# Druckluftelektrik.net
KiCad netlist of a schematic drawn in EAGLE
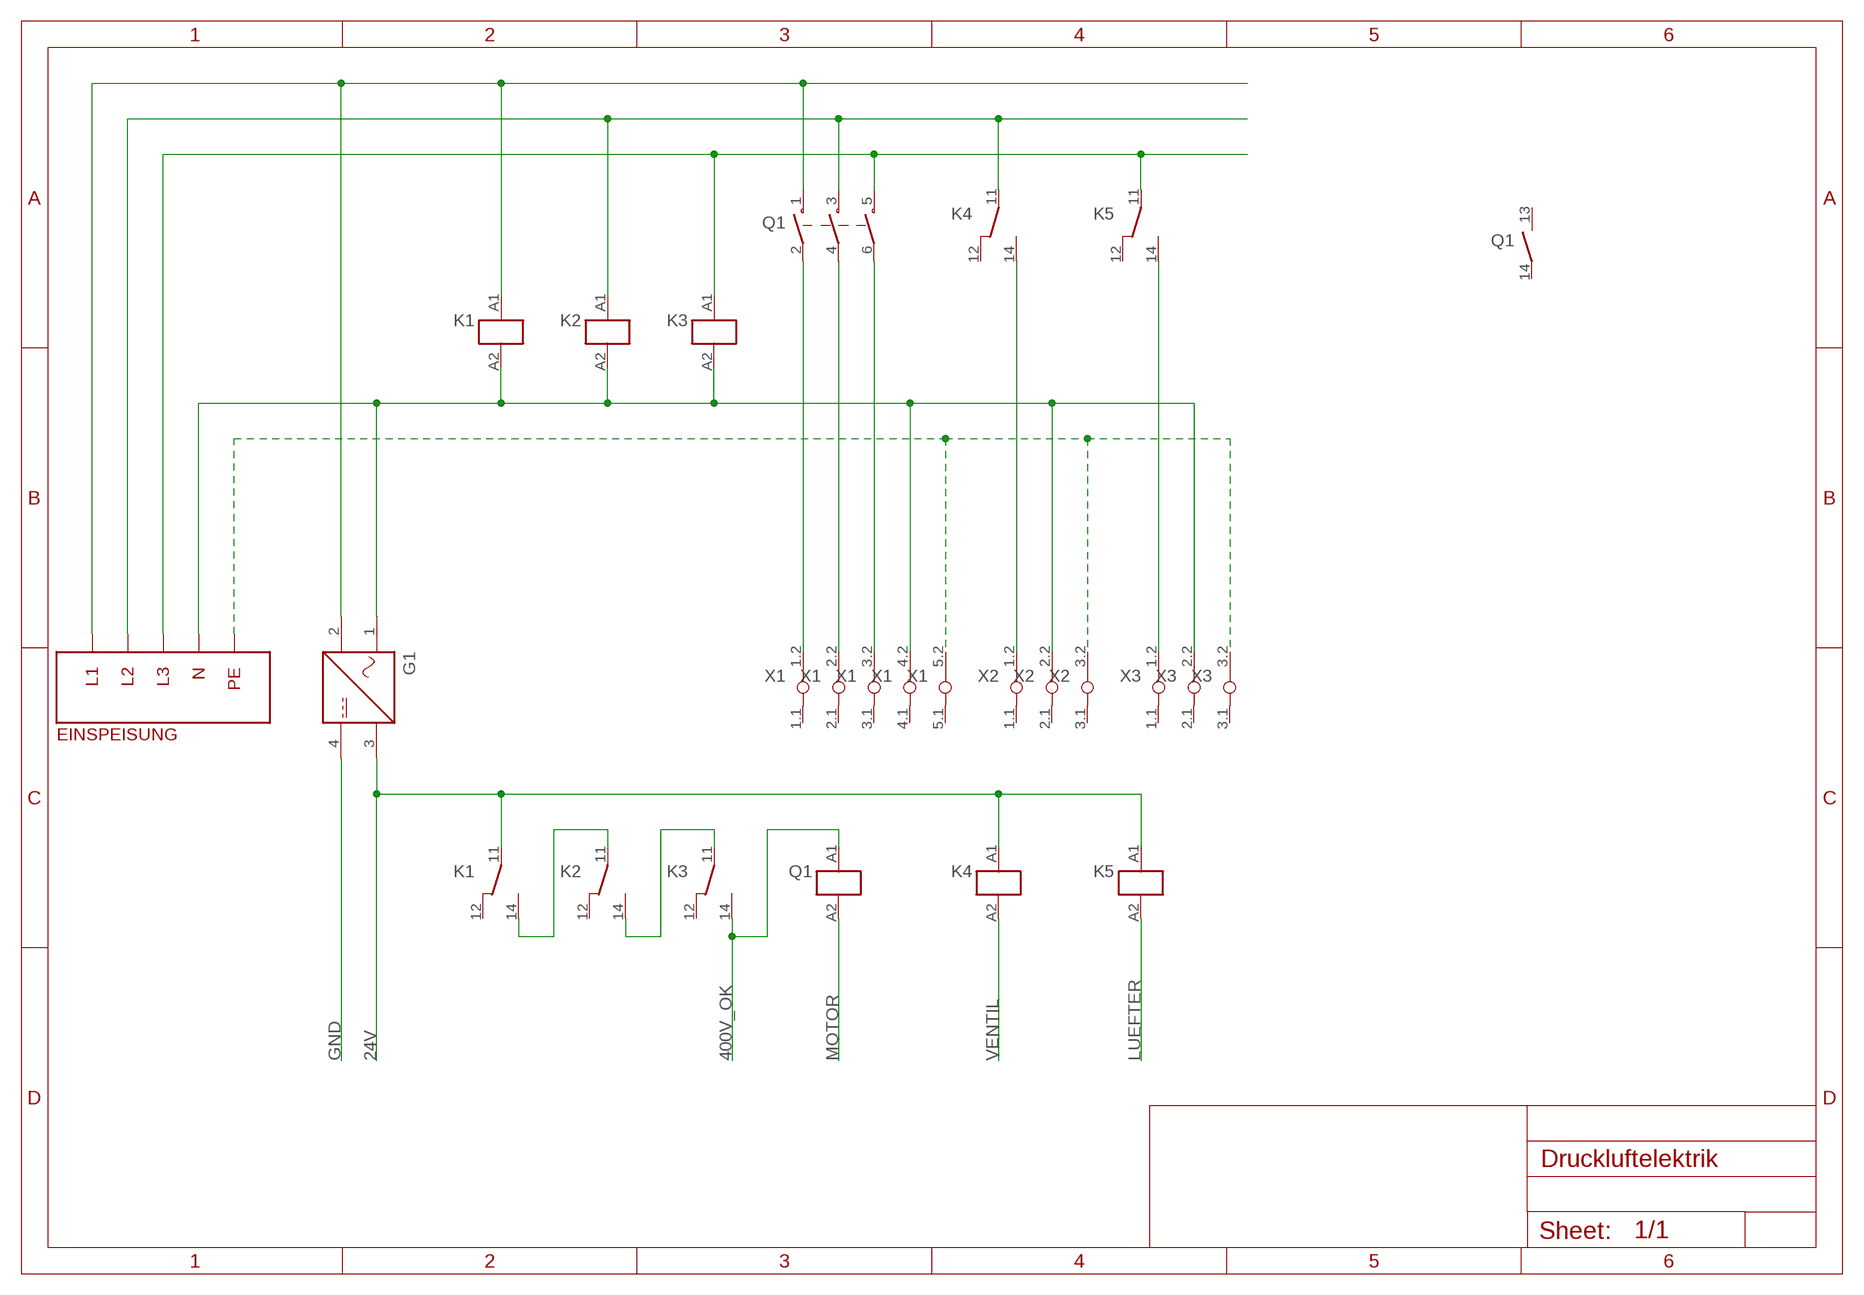
[diagram p0: schematic, sheet 1]

(export (version "E")
  (design (tool "Eeschema 10.0.6"))
  (components
    (comp (ref "G1")
      (value "NETZTEIL_GLEICHSPANNUNG")
      (footprint "eagle-import:NETZTEIL_GLEICHSPANNUNG")
      (libsource (lib "eagle-import") (part "NETZTEIL_GLEICHSPANNUNG"))
    )
    (comp (ref "K1")
      (value "HILFSSCHUETZ_11-12-14")
      (footprint "eagle-import:HILFSSCHUETZ_11-12-14")
      (libsource (lib "eagle-import") (part "HILFSSCHUETZ_11-12-14"))
    )
    (comp (ref "K2")
      (value "HILFSSCHUETZ_11-12-14")
      (footprint "eagle-import:HILFSSCHUETZ_11-12-14")
      (libsource (lib "eagle-import") (part "HILFSSCHUETZ_11-12-14"))
    )
    (comp (ref "K3")
      (value "HILFSSCHUETZ_11-12-14")
      (footprint "eagle-import:HILFSSCHUETZ_11-12-14")
      (libsource (lib "eagle-import") (part "HILFSSCHUETZ_11-12-14"))
    )
    (comp (ref "K4")
      (value "HILFSSCHUETZ_11-12-14")
      (footprint "eagle-import:HILFSSCHUETZ_11-12-14")
      (libsource (lib "eagle-import") (part "HILFSSCHUETZ_11-12-14"))
    )
    (comp (ref "K5")
      (value "HILFSSCHUETZ_11-12-14")
      (footprint "eagle-import:HILFSSCHUETZ_11-12-14")
      (libsource (lib "eagle-import") (part "HILFSSCHUETZ_11-12-14"))
    )
    (comp (ref "Q1")
      (value "HAUPTSCHUETZ_3-POL_HILFSKONTAKT_13-14")
      (footprint "eagle-import:HAUPTSCHUETZ_3-POL+HILFSKONTAKT_13-14")
      (libsource (lib "eagle-import") (part "HAUPTSCHUETZ_3-POL_HILFSKONTAKT_13-14"))
    )
    (comp (ref "X1")
      (value "KLEMME_1-5")
      (footprint "eagle-import:KLEMME_1-5")
      (libsource (lib "eagle-import") (part "KLEMME_1-5"))
    )
    (comp (ref "X2")
      (value "KLEMME_1-3")
      (footprint "eagle-import:KLEMME_1-3")
      (libsource (lib "eagle-import") (part "KLEMME_1-3"))
    )
    (comp (ref "X3")
      (value "KLEMME_1-3")
      (footprint "eagle-import:KLEMME_1-3")
      (libsource (lib "eagle-import") (part "KLEMME_1-3"))
    )
  )
  (nets
    (net (code "1") (name "/24V") (class "Default")
      (node (ref "G1") (pin "3") (pinfunction "3_3") (pintype "passive"))
      (node (ref "K1") (pin "11") (pinfunction "1_11") (pintype "passive"))
      (node (ref "K4") (pin "A1") (pinfunction "A1_A1") (pintype "input"))
      (node (ref "K5") (pin "A1") (pinfunction "A1_A1") (pintype "input"))
    )
    (net (code "2") (name "/400V_OK") (class "Default")
      (node (ref "K3") (pin "14") (pinfunction "4_14") (pintype "passive"))
      (node (ref "Q1") (pin "A1") (pinfunction "A1_A1") (pintype "input"))
    )
    (net (code "3") (name "/GND") (class "Default")
      (node (ref "G1") (pin "4") (pinfunction "4_4") (pintype "passive"))
    )
    (net (code "4") (name "/LUEFTER") (class "Default")
      (node (ref "K5") (pin "A2") (pinfunction "A2_A2") (pintype "input"))
    )
    (net (code "5") (name "/MOTOR") (class "Default")
      (node (ref "Q1") (pin "A2") (pinfunction "A2_A2") (pintype "input"))
    )
    (net (code "6") (name "/VENTIL") (class "Default")
      (node (ref "K4") (pin "A2") (pinfunction "A2_A2") (pintype "input"))
    )
    (net (code "7") (name "Net-(G1-Pad1)") (class "Default")
      (node (ref "G1") (pin "1") (pinfunction "1_1") (pintype "passive"))
      (node (ref "K1") (pin "A2") (pinfunction "A2_A2") (pintype "input"))
      (node (ref "K2") (pin "A2") (pinfunction "A2_A2") (pintype "input"))
      (node (ref "K3") (pin "A2") (pinfunction "A2_A2") (pintype "input"))
      (node (ref "X1") (pin "4.2") (pinfunction "4.2_4.2") (pintype "passive"))
      (node (ref "X2") (pin "2.2") (pinfunction "2.2_2.2") (pintype "passive"))
      (node (ref "X3") (pin "2.2") (pinfunction "2.2_2.2") (pintype "passive"))
    )
    (net (code "8") (name "Net-(G1-Pad2)") (class "Default")
      (node (ref "G1") (pin "2") (pinfunction "2_2") (pintype "passive"))
      (node (ref "K1") (pin "A1") (pinfunction "A1_A1") (pintype "input"))
      (node (ref "Q1") (pin "1") (pinfunction "1_1") (pintype "passive"))
    )
    (net (code "9") (name "Net-(K1B-4)") (class "Default")
      (node (ref "K1") (pin "14") (pinfunction "4_14") (pintype "passive"))
      (node (ref "K2") (pin "11") (pinfunction "1_11") (pintype "passive"))
    )
    (net (code "10") (name "Net-(K2B-4)") (class "Default")
      (node (ref "K2") (pin "14") (pinfunction "4_14") (pintype "passive"))
      (node (ref "K3") (pin "11") (pinfunction "1_11") (pintype "passive"))
    )
    (net (code "11") (name "Net-(K4B-1)") (class "Default")
      (node (ref "K2") (pin "A1") (pinfunction "A1_A1") (pintype "input"))
      (node (ref "K4") (pin "11") (pinfunction "1_11") (pintype "passive"))
      (node (ref "Q1") (pin "3") (pinfunction "3_3") (pintype "passive"))
    )
    (net (code "12") (name "Net-(K4B-4)") (class "Default")
      (node (ref "K4") (pin "14") (pinfunction "4_14") (pintype "passive"))
      (node (ref "X2") (pin "1.2") (pinfunction "1.2_1.2") (pintype "passive"))
    )
    (net (code "13") (name "Net-(K5B-1)") (class "Default")
      (node (ref "K3") (pin "A1") (pinfunction "A1_A1") (pintype "input"))
      (node (ref "K5") (pin "11") (pinfunction "1_11") (pintype "passive"))
      (node (ref "Q1") (pin "5") (pinfunction "5_5") (pintype "passive"))
    )
    (net (code "14") (name "Net-(K5B-4)") (class "Default")
      (node (ref "K5") (pin "14") (pinfunction "4_14") (pintype "passive"))
      (node (ref "X3") (pin "1.2") (pinfunction "1.2_1.2") (pintype "passive"))
    )
    (net (code "15") (name "Net-(Q1-Pad2)") (class "Default")
      (node (ref "Q1") (pin "2") (pinfunction "2_2") (pintype "passive"))
      (node (ref "X1") (pin "1.2") (pinfunction "1.2_1.2") (pintype "passive"))
    )
    (net (code "16") (name "Net-(Q1-Pad4)") (class "Default")
      (node (ref "Q1") (pin "4") (pinfunction "4_4") (pintype "passive"))
      (node (ref "X1") (pin "2.2") (pinfunction "2.2_2.2") (pintype "passive"))
    )
    (net (code "17") (name "Net-(Q1-Pad6)") (class "Default")
      (node (ref "Q1") (pin "6") (pinfunction "6_6") (pintype "passive"))
      (node (ref "X1") (pin "3.2") (pinfunction "3.2_3.2") (pintype "passive"))
    )
    (net (code "18") (name "Net-(X1-Pad5.2)") (class "Default")
      (node (ref "X1") (pin "5.2") (pinfunction "5.2_5.2") (pintype "passive"))
      (node (ref "X2") (pin "3.2") (pinfunction "3.2_3.2") (pintype "passive"))
      (node (ref "X3") (pin "3.2") (pinfunction "3.2_3.2") (pintype "passive"))
    )
    (net (code "19") (name "unconnected-(K1B-2-Pad12)") (class "Default")
      (node (ref "K1") (pin "12") (pinfunction "2_12") (pintype "passive"))
    )
    (net (code "20") (name "unconnected-(K2B-2-Pad12)") (class "Default")
      (node (ref "K2") (pin "12") (pinfunction "2_12") (pintype "passive"))
    )
    (net (code "21") (name "unconnected-(K3B-2-Pad12)") (class "Default")
      (node (ref "K3") (pin "12") (pinfunction "2_12") (pintype "passive"))
    )
    (net (code "22") (name "unconnected-(K4B-2-Pad12)") (class "Default")
      (node (ref "K4") (pin "12") (pinfunction "2_12") (pintype "passive"))
    )
    (net (code "23") (name "unconnected-(K5B-2-Pad12)") (class "Default")
      (node (ref "K5") (pin "12") (pinfunction "2_12") (pintype "passive"))
    )
    (net (code "24") (name "unconnected-(Q1B-3-Pad13)") (class "Default")
      (node (ref "Q1") (pin "13") (pinfunction "3_13") (pintype "passive"))
    )
    (net (code "25") (name "unconnected-(Q1B-4-Pad14)") (class "Default")
      (node (ref "Q1") (pin "14") (pinfunction "4_14") (pintype "passive"))
    )
    (net (code "26") (name "unconnected-(X1-Pad1.1)") (class "Default")
      (node (ref "X1") (pin "1.1") (pinfunction "1.1_1.1") (pintype "passive"))
    )
    (net (code "27") (name "unconnected-(X1-Pad2.1)") (class "Default")
      (node (ref "X1") (pin "2.1") (pinfunction "2.1_2.1") (pintype "passive"))
    )
    (net (code "28") (name "unconnected-(X1-Pad3.1)") (class "Default")
      (node (ref "X1") (pin "3.1") (pinfunction "3.1_3.1") (pintype "passive"))
    )
    (net (code "29") (name "unconnected-(X1-Pad4.1)") (class "Default")
      (node (ref "X1") (pin "4.1") (pinfunction "4.1_4.1") (pintype "passive"))
    )
    (net (code "30") (name "unconnected-(X1-Pad5.1)") (class "Default")
      (node (ref "X1") (pin "5.1") (pinfunction "5.1_5.1") (pintype "passive"))
    )
    (net (code "31") (name "unconnected-(X2-Pad1.1)") (class "Default")
      (node (ref "X2") (pin "1.1") (pinfunction "1.1_1.1") (pintype "passive"))
    )
    (net (code "32") (name "unconnected-(X2-Pad2.1)") (class "Default")
      (node (ref "X2") (pin "2.1") (pinfunction "2.1_2.1") (pintype "passive"))
    )
    (net (code "33") (name "unconnected-(X2-Pad3.1)") (class "Default")
      (node (ref "X2") (pin "3.1") (pinfunction "3.1_3.1") (pintype "passive"))
    )
    (net (code "34") (name "unconnected-(X3-Pad1.1)") (class "Default")
      (node (ref "X3") (pin "1.1") (pinfunction "1.1_1.1") (pintype "passive"))
    )
    (net (code "35") (name "unconnected-(X3-Pad2.1)") (class "Default")
      (node (ref "X3") (pin "2.1") (pinfunction "2.1_2.1") (pintype "passive"))
    )
    (net (code "36") (name "unconnected-(X3-Pad3.1)") (class "Default")
      (node (ref "X3") (pin "3.1") (pinfunction "3.1_3.1") (pintype "passive"))
    )
  )
)
